# stop_circuit.net
KiCad netlist of a schematic drawn in EAGLE
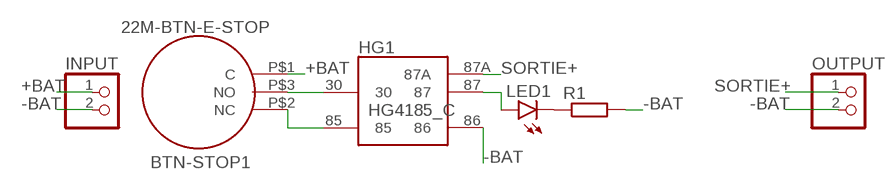
[diagram p0: schematic, sheet 1]

(export (version "E")
  (design (tool "Eeschema 10.0.6"))
  (components
    (comp (ref "BTN-STOP1")
      (value "22M-BTN-E-STOP")
      (footprint "eagle-import:22MM-BTN-E-STOP")
      (libsource (lib "eagle-import") (part "22M-BTN-E-STOP"))
    )
    (comp (ref "HG1")
      (value "HG4185_C")
      (footprint "eagle-import:HG4185_C_1Z")
      (libsource (lib "eagle-import") (part "HG4185_C"))
    )
    (comp (ref "INPUT")
      (value "PINHD-1X2")
      (footprint "eagle-import:1X02")
      (libsource (lib "eagle-import") (part "PINHD-1X2"))
    )
    (comp (ref "LED1")
      (value "LEDB156")
      (footprint "eagle-import:Q62902-B156")
      (libsource (lib "eagle-import") (part "LEDB156"))
    )
    (comp (ref "OUTPUT")
      (value "PINHD-1X2")
      (footprint "eagle-import:1X02")
      (libsource (lib "eagle-import") (part "PINHD-1X2"))
    )
    (comp (ref "R1")
      (value "R-EU_0204/7")
      (footprint "eagle-import:0204_7")
      (libsource (lib "eagle-import") (part "R-EU_0204/7"))
    )
  )
  (nets
    (net (code "1") (name "/+BAT") (class "Default")
      (node (ref "BTN-STOP1") (pin "P$1") (pinfunction "C_P$1") (pintype "bidirectional"))
      (node (ref "INPUT") (pin "1") (pinfunction "1_1") (pintype "passive"))
    )
    (net (code "2") (name "/-BAT") (class "Default")
      (node (ref "HG1") (pin "86") (pinfunction "86_86") (pintype "bidirectional"))
      (node (ref "INPUT") (pin "2") (pinfunction "2_2") (pintype "passive"))
      (node (ref "OUTPUT") (pin "2") (pinfunction "2_2") (pintype "passive"))
      (node (ref "R1") (pin "2") (pinfunction "2_2") (pintype "passive"))
    )
    (net (code "3") (name "/SORTIE+") (class "Default")
      (node (ref "HG1") (pin "87A") (pinfunction "87A_87A") (pintype "bidirectional"))
      (node (ref "OUTPUT") (pin "1") (pinfunction "1_1") (pintype "passive"))
    )
    (net (code "4") (name "Net-(BTN-STOP1-NC)") (class "Default")
      (node (ref "BTN-STOP1") (pin "P$2") (pinfunction "NC_P$2") (pintype "bidirectional"))
      (node (ref "HG1") (pin "85") (pinfunction "85_85") (pintype "bidirectional"))
    )
    (net (code "5") (name "Net-(BTN-STOP1-NO)") (class "Default")
      (node (ref "BTN-STOP1") (pin "P$3") (pinfunction "NO_P$3") (pintype "bidirectional"))
      (node (ref "HG1") (pin "30") (pinfunction "30_30") (pintype "bidirectional"))
    )
    (net (code "6") (name "Net-(HG1-Pad87)") (class "Default")
      (node (ref "HG1") (pin "87") (pinfunction "87_87") (pintype "bidirectional"))
      (node (ref "LED1") (pin "A") (pinfunction "A_A") (pintype "passive"))
    )
    (net (code "7") (name "Net-(LED1-C)") (class "Default")
      (node (ref "LED1") (pin "K") (pinfunction "C_K") (pintype "passive"))
      (node (ref "R1") (pin "1") (pinfunction "1_1") (pintype "passive"))
    )
  )
)
